# RS485_CAN.net
KiCad netlist of a schematic drawn in Altium Designer
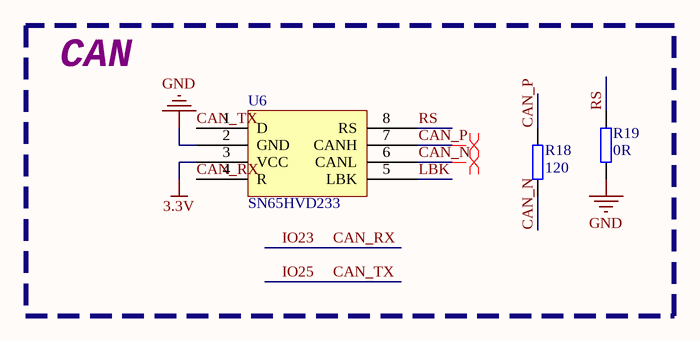
[diagram p0: RS485_CAN.SchDoc]

(export (version "E")
  (design (tool "Eeschema 10.0.6"))
  (components
    (comp (ref "R18")
      (value "120")
      (footprint "SMT0603")
      (description "RES SM 0603 10K")
      (fields (field (name "Comment") "Resistor"))
      (libsource (lib "electronpowered") (part "RES-SM-0603-10K"))
    )
    (comp (ref "R19")
      (value "0R")
      (footprint "SMT0603")
      (description "RES SM 0603 10K")
      (fields (field (name "Comment") "Resistor"))
      (libsource (lib "electronpowered") (part "RES-SM-0603-10K"))
    )
    (comp (ref "U6")
      (value "SN65HVD233")
      (footprint "PCBComponent_1")
      (libsource (lib "SN65HVD233") (part "SN65HVD233"))
    )
  )
  (nets
    (net (code "1") (name "/CAN_N") (class "Default")
      (node (ref "R18") (pin "1") (pinfunction "1_1") (pintype "passive"))
      (node (ref "U6") (pin "6") (pinfunction "CANL_6") (pintype "passive"))
    )
    (net (code "2") (name "/CAN_P") (class "Default")
      (node (ref "R18") (pin "2") (pinfunction "2_2") (pintype "passive"))
      (node (ref "U6") (pin "7") (pinfunction "CANH_7") (pintype "passive"))
    )
    (net (code "3") (name "/CAN_RX") (class "Default")
      (node (ref "U6") (pin "4") (pinfunction "R_4") (pintype "passive"))
    )
    (net (code "4") (name "/CAN_TX") (class "Default")
      (node (ref "U6") (pin "1") (pinfunction "D_1") (pintype "passive"))
    )
    (net (code "5") (name "/LBK") (class "Default")
      (node (ref "U6") (pin "5") (pinfunction "LBK_5") (pintype "passive"))
    )
    (net (code "6") (name "/RS") (class "Default")
      (node (ref "R19") (pin "2") (pinfunction "2_2") (pintype "passive"))
      (node (ref "U6") (pin "8") (pinfunction "RS_8") (pintype "passive"))
    )
    (net (code "7") (name "3.3V") (class "Default")
      (node (ref "U6") (pin "3") (pinfunction "VCC_3") (pintype "passive"))
    )
    (net (code "8") (name "GND") (class "Default")
      (node (ref "R19") (pin "1") (pinfunction "1_1") (pintype "passive"))
      (node (ref "U6") (pin "2") (pinfunction "GND_2") (pintype "passive"))
    )
  )
)
